# MRCS-Morse-Code-Buzzer-Controller.net
KiCad netlist of a schematic drawn in EAGLE
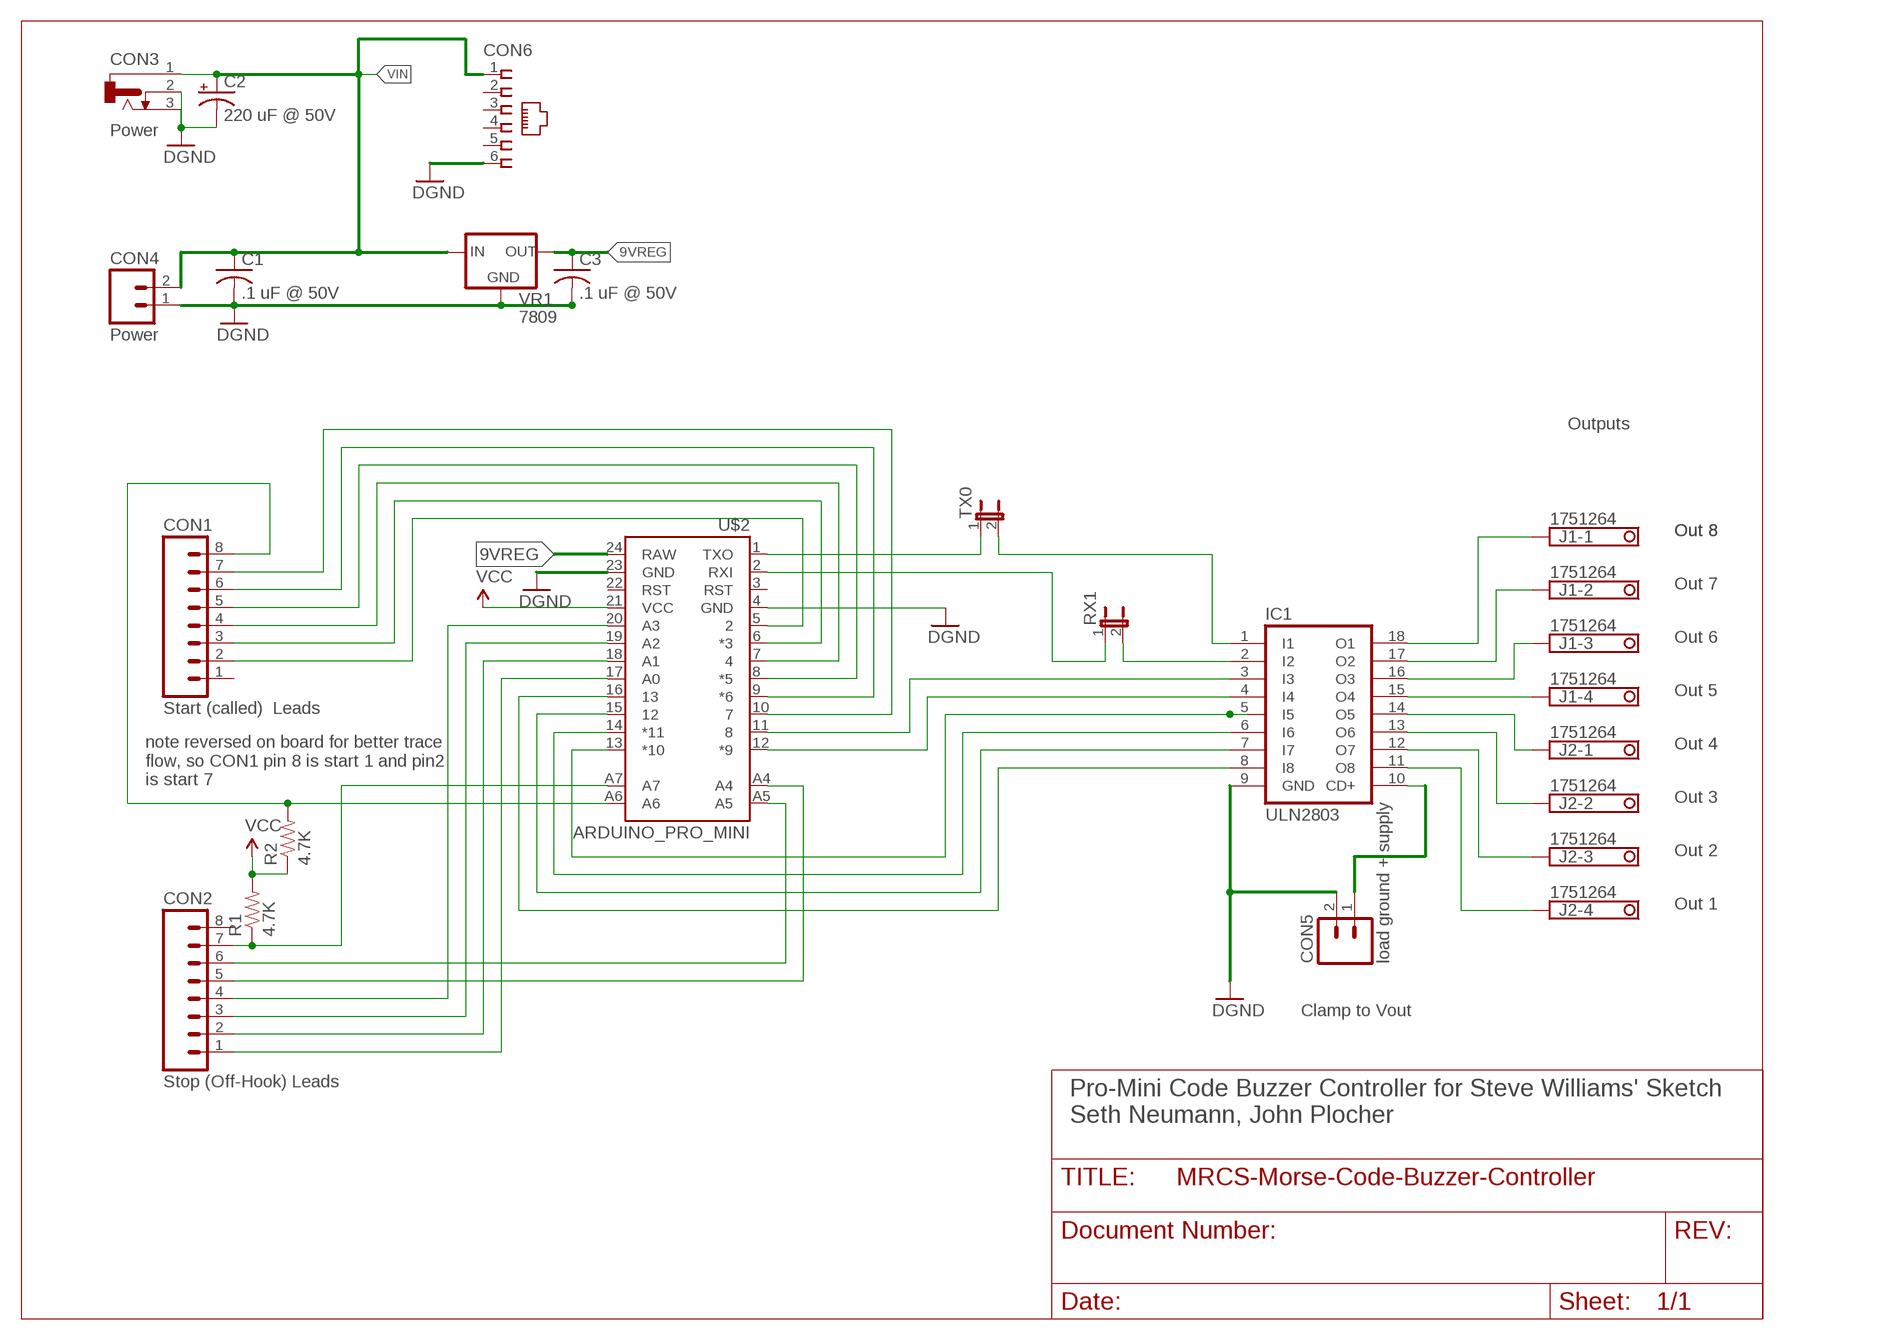
[diagram p0: schematic, sheet 1]

(export (version "E")
  (design (tool "Eeschema 10.0.6"))
  (components
    (comp (ref "C1")
      (value ".1 uF @ 50V")
      (footprint "eagle-import:C025-030X050")
      (libsource (lib "eagle-import") (part "C-US025-030X050"))
    )
    (comp (ref "C2")
      (value "220 uF @ 50V")
      (footprint "eagle-import:E3,5-10")
      (libsource (lib "eagle-import") (part "CPOL-USE3.5-10"))
    )
    (comp (ref "C3")
      (value ".1 uF @ 50V")
      (footprint "eagle-import:C025-030X050")
      (libsource (lib "eagle-import") (part "C-US025-030X050"))
    )
    (comp (ref "CON1")
      (value "Start (called) Leads")
      (footprint "eagle-import:1X08_LOCK")
      (libsource (lib "eagle-import") (part "CONNECTOR-M08LOCK"))
    )
    (comp (ref "CON2")
      (value "Stop (Off-Hook) Leads")
      (footprint "eagle-import:1X08_LOCK")
      (libsource (lib "eagle-import") (part "CONNECTOR-M08LOCK"))
    )
    (comp (ref "CON3")
      (value "Power")
      (footprint "eagle-import:DCJ0202")
      (libsource (lib "eagle-import") (part "CONNECTOR-DC-POWER-RA"))
    )
    (comp (ref "CON4")
      (value "Power")
      (footprint "eagle-import:MSTB2")
      (libsource (lib "eagle-import") (part "CONNECTOR-M02508-LOCK"))
    )
    (comp (ref "CON5")
      (value "load ground + supply")
      (footprint "eagle-import:MSTB2")
      (libsource (lib "eagle-import") (part "CONNECTOR-M02508-LOCK"))
    )
    (comp (ref "CON6")
      (value "CONNECTOR-RJ25-43860-2-MOLEX")
      (footprint "eagle-import:RJ25-INVERTED")
      (libsource (lib "eagle-import") (part "CONNECTOR-RJ25-43860-2-MOLEX"))
    )
    (comp (ref "IC1")
      (value "ULN2803")
      (footprint "eagle-import:DIL18")
      (libsource (lib "eagle-import") (part "ULN2803A"))
    )
    (comp (ref "J1")
      (value "1751264")
      (footprint "eagle-import:1751264")
      (libsource (lib "eagle-import") (part "1751264"))
    )
    (comp (ref "J2")
      (value "1751264")
      (footprint "eagle-import:1751264")
      (libsource (lib "eagle-import") (part "1751264"))
    )
    (comp (ref "R1")
      (value "4.7K")
      (footprint "eagle-import:AXIAL-0.4-RES")
      (libsource (lib "eagle-import") (part "RPTH04"))
    )
    (comp (ref "R2")
      (value "4.7K")
      (footprint "eagle-import:AXIAL-0.4-RES")
      (libsource (lib "eagle-import") (part "RPTH04"))
    )
    (comp (ref "RX1")
      (value "JUMPER-2PTH")
      (footprint "eagle-import:1X02")
      (libsource (lib "eagle-import") (part "JUMPER-2PTH"))
    )
    (comp (ref "TX0")
      (value "JUMPER-2PTH")
      (footprint "eagle-import:1X02")
      (libsource (lib "eagle-import") (part "JUMPER-2PTH"))
    )
    (comp (ref "U$2")
      (value "ARDUINO_PRO_MINI")
      (footprint "eagle-import:ARDUINO_PRO_MINI")
      (libsource (lib "eagle-import") (part "ARDUINO_PRO_MINI"))
    )
    (comp (ref "VR1")
      (value "7809")
      (footprint "eagle-import:TO-220-RA-SINK")
      (libsource (lib "eagle-import") (part "VREG-?-PTH-RA9"))
    )
  )
  (nets
    (net (code "1") (name "9VREG") (class "Default")
      (node (ref "C3") (pin "1") (pinfunction "1_1") (pintype "passive"))
      (node (ref "U$2") (pin "24") (pinfunction "RAW_24") (pintype "bidirectional"))
      (node (ref "VR1") (pin "OUT") (pinfunction "OUT_OUT") (pintype "output"))
    )
    (net (code "2") (name "DGND") (class "Default")
      (node (ref "C1") (pin "2") (pinfunction "2_2") (pintype "passive"))
      (node (ref "C2") (pin "-") (pinfunction "-_-") (pintype "passive"))
      (node (ref "C3") (pin "2") (pinfunction "2_2") (pintype "passive"))
      (node (ref "CON3") (pin "2") (pinfunction "2_2") (pintype "passive"))
      (node (ref "CON3") (pin "3") (pinfunction "3_3") (pintype "passive"))
      (node (ref "CON4") (pin "1") (pinfunction "1_1") (pintype "passive"))
      (node (ref "CON5") (pin "2") (pinfunction "2_2") (pintype "passive"))
      (node (ref "CON6") (pin "6") (pinfunction "6_6") (pintype "passive"))
      (node (ref "IC1") (pin "9") (pinfunction "GND_9") (pintype "power_in"))
      (node (ref "U$2") (pin "23") (pinfunction "GND_23") (pintype "bidirectional"))
      (node (ref "U$2") (pin "4") (pinfunction "GND_4") (pintype "bidirectional"))
      (node (ref "VR1") (pin "GND") (pinfunction "GND_GND") (pintype "input"))
    )
    (net (code "3") (name "Net-(CON2-Pad5)") (class "Default")
      (node (ref "CON2") (pin "5") (pinfunction "5_5") (pintype "passive"))
      (node (ref "U$2") (pin "A4") (pinfunction "A4_A4") (pintype "bidirectional"))
    )
    (net (code "4") (name "Net-(CON2-Pad6)") (class "Default")
      (node (ref "CON2") (pin "6") (pinfunction "6_6") (pintype "passive"))
      (node (ref "U$2") (pin "A5") (pinfunction "A5_A5") (pintype "bidirectional"))
    )
    (net (code "5") (name "Net-(IC1-CD+)") (class "Default")
      (node (ref "CON5") (pin "1") (pinfunction "1_1") (pintype "passive"))
      (node (ref "IC1") (pin "10") (pinfunction "CD+_10") (pintype "passive"))
    )
    (net (code "6") (name "Net-(IC1-I1)") (class "Default")
      (node (ref "IC1") (pin "1") (pinfunction "I1_1") (pintype "input"))
      (node (ref "TX0") (pin "2") (pinfunction "2_2") (pintype "passive"))
    )
    (net (code "7") (name "Net-(IC1-I2)") (class "Default")
      (node (ref "IC1") (pin "2") (pinfunction "I2_2") (pintype "input"))
      (node (ref "RX1") (pin "2") (pinfunction "2_2") (pintype "passive"))
    )
    (net (code "8") (name "Net-(IC1-I3)") (class "Default")
      (node (ref "IC1") (pin "3") (pinfunction "I3_3") (pintype "input"))
      (node (ref "U$2") (pin "11") (pinfunction "8_11") (pintype "bidirectional"))
    )
    (net (code "9") (name "Net-(IC1-I4)") (class "Default")
      (node (ref "IC1") (pin "4") (pinfunction "I4_4") (pintype "input"))
      (node (ref "U$2") (pin "12") (pinfunction "*9_12") (pintype "bidirectional"))
    )
    (net (code "10") (name "Net-(IC1-I5)") (class "Default")
      (node (ref "IC1") (pin "5") (pinfunction "I5_5") (pintype "input"))
      (node (ref "U$2") (pin "13") (pinfunction "*10_13") (pintype "bidirectional"))
    )
    (net (code "11") (name "Net-(IC1-I6)") (class "Default")
      (node (ref "IC1") (pin "6") (pinfunction "I6_6") (pintype "input"))
      (node (ref "U$2") (pin "14") (pinfunction "*11_14") (pintype "bidirectional"))
    )
    (net (code "12") (name "Net-(IC1-I7)") (class "Default")
      (node (ref "IC1") (pin "7") (pinfunction "I7_7") (pintype "input"))
      (node (ref "U$2") (pin "15") (pinfunction "12_15") (pintype "bidirectional"))
    )
    (net (code "13") (name "Net-(IC1-I8)") (class "Default")
      (node (ref "IC1") (pin "8") (pinfunction "I8_8") (pintype "input"))
      (node (ref "U$2") (pin "16") (pinfunction "13_16") (pintype "bidirectional"))
    )
    (net (code "14") (name "Net-(IC1-O1)") (class "Default")
      (node (ref "IC1") (pin "18") (pinfunction "O1_18") (pintype "open_collector"))
      (node (ref "J1") (pin "1") (pinfunction "K_1") (pintype "passive"))
    )
    (net (code "15") (name "Net-(IC1-O2)") (class "Default")
      (node (ref "IC1") (pin "17") (pinfunction "O2_17") (pintype "open_collector"))
      (node (ref "J1") (pin "2") (pinfunction "K_2") (pintype "passive"))
    )
    (net (code "16") (name "Net-(IC1-O3)") (class "Default")
      (node (ref "IC1") (pin "16") (pinfunction "O3_16") (pintype "open_collector"))
      (node (ref "J1") (pin "3") (pinfunction "K_3") (pintype "passive"))
    )
    (net (code "17") (name "Net-(IC1-O4)") (class "Default")
      (node (ref "IC1") (pin "15") (pinfunction "O4_15") (pintype "open_collector"))
      (node (ref "J1") (pin "4") (pinfunction "K_4") (pintype "passive"))
    )
    (net (code "18") (name "Net-(IC1-O5)") (class "Default")
      (node (ref "IC1") (pin "14") (pinfunction "O5_14") (pintype "open_collector"))
      (node (ref "J2") (pin "1") (pinfunction "K_1") (pintype "passive"))
    )
    (net (code "19") (name "Net-(IC1-O6)") (class "Default")
      (node (ref "IC1") (pin "13") (pinfunction "O6_13") (pintype "open_collector"))
      (node (ref "J2") (pin "2") (pinfunction "K_2") (pintype "passive"))
    )
    (net (code "20") (name "Net-(IC1-O7)") (class "Default")
      (node (ref "IC1") (pin "12") (pinfunction "O7_12") (pintype "open_collector"))
      (node (ref "J2") (pin "3") (pinfunction "K_3") (pintype "passive"))
    )
    (net (code "21") (name "Net-(IC1-O8)") (class "Default")
      (node (ref "IC1") (pin "11") (pinfunction "O8_11") (pintype "open_collector"))
      (node (ref "J2") (pin "4") (pinfunction "K_4") (pintype "passive"))
    )
    (net (code "22") (name "Net-(R1-1)") (class "Default")
      (node (ref "CON2") (pin "7") (pinfunction "7_7") (pintype "passive"))
      (node (ref "R1") (pin "P$1") (pinfunction "1_P$1") (pintype "passive"))
      (node (ref "U$2") (pin "A7") (pinfunction "A7_A7") (pintype "bidirectional"))
    )
    (net (code "23") (name "Net-(R2-2)") (class "Default")
      (node (ref "CON1") (pin "8") (pinfunction "8_8") (pintype "passive"))
      (node (ref "R2") (pin "P$2") (pinfunction "2_P$2") (pintype "passive"))
      (node (ref "U$2") (pin "A6") (pinfunction "A6_A6") (pintype "bidirectional"))
    )
    (net (code "24") (name "Net-(U$2-*3)") (class "Default")
      (node (ref "CON1") (pin "3") (pinfunction "3_3") (pintype "passive"))
      (node (ref "U$2") (pin "6") (pinfunction "*3_6") (pintype "bidirectional"))
    )
    (net (code "25") (name "Net-(U$2-*5)") (class "Default")
      (node (ref "CON1") (pin "5") (pinfunction "5_5") (pintype "passive"))
      (node (ref "U$2") (pin "8") (pinfunction "*5_8") (pintype "bidirectional"))
    )
    (net (code "26") (name "Net-(U$2-*6)") (class "Default")
      (node (ref "CON1") (pin "6") (pinfunction "6_6") (pintype "passive"))
      (node (ref "U$2") (pin "9") (pinfunction "*6_9") (pintype "bidirectional"))
    )
    (net (code "27") (name "Net-(U$2-2)") (class "Default")
      (node (ref "CON1") (pin "2") (pinfunction "2_2") (pintype "passive"))
      (node (ref "U$2") (pin "5") (pinfunction "2_5") (pintype "bidirectional"))
    )
    (net (code "28") (name "Net-(U$2-4)") (class "Default")
      (node (ref "CON1") (pin "4") (pinfunction "4_4") (pintype "passive"))
      (node (ref "U$2") (pin "7") (pinfunction "4_7") (pintype "bidirectional"))
    )
    (net (code "29") (name "Net-(U$2-7)") (class "Default")
      (node (ref "CON1") (pin "7") (pinfunction "7_7") (pintype "passive"))
      (node (ref "U$2") (pin "10") (pinfunction "7_10") (pintype "bidirectional"))
    )
    (net (code "30") (name "Net-(U$2-A0)") (class "Default")
      (node (ref "CON2") (pin "1") (pinfunction "1_1") (pintype "passive"))
      (node (ref "U$2") (pin "17") (pinfunction "A0_17") (pintype "bidirectional"))
    )
    (net (code "31") (name "Net-(U$2-A1)") (class "Default")
      (node (ref "CON2") (pin "2") (pinfunction "2_2") (pintype "passive"))
      (node (ref "U$2") (pin "18") (pinfunction "A1_18") (pintype "bidirectional"))
    )
    (net (code "32") (name "Net-(U$2-A2)") (class "Default")
      (node (ref "CON2") (pin "3") (pinfunction "3_3") (pintype "passive"))
      (node (ref "U$2") (pin "19") (pinfunction "A2_19") (pintype "bidirectional"))
    )
    (net (code "33") (name "Net-(U$2-A3)") (class "Default")
      (node (ref "CON2") (pin "4") (pinfunction "4_4") (pintype "passive"))
      (node (ref "U$2") (pin "20") (pinfunction "A3_20") (pintype "bidirectional"))
    )
    (net (code "34") (name "Net-(U$2-RXI)") (class "Default")
      (node (ref "RX1") (pin "1") (pinfunction "1_1") (pintype "passive"))
      (node (ref "U$2") (pin "2") (pinfunction "RXI_2") (pintype "bidirectional"))
    )
    (net (code "35") (name "Net-(U$2-TXO)") (class "Default")
      (node (ref "TX0") (pin "1") (pinfunction "1_1") (pintype "passive"))
      (node (ref "U$2") (pin "1") (pinfunction "TXO_1") (pintype "bidirectional"))
    )
    (net (code "36") (name "VCC") (class "Default")
      (node (ref "R1") (pin "P$2") (pinfunction "2_P$2") (pintype "passive"))
      (node (ref "R2") (pin "P$1") (pinfunction "1_P$1") (pintype "passive"))
      (node (ref "U$2") (pin "21") (pinfunction "VCC_21") (pintype "bidirectional"))
    )
    (net (code "37") (name "VIN") (class "Default")
      (node (ref "C1") (pin "1") (pinfunction "1_1") (pintype "passive"))
      (node (ref "C2") (pin "+") (pinfunction "+_+") (pintype "passive"))
      (node (ref "CON3") (pin "1") (pinfunction "1_1") (pintype "passive"))
      (node (ref "CON4") (pin "2") (pinfunction "2_2") (pintype "passive"))
      (node (ref "CON6") (pin "1") (pinfunction "1_1") (pintype "passive"))
      (node (ref "VR1") (pin "IN") (pinfunction "IN_IN") (pintype "input"))
    )
    (net (code "38") (name "unconnected-(CON1-Pad1)") (class "Default")
      (node (ref "CON1") (pin "1") (pinfunction "1_1") (pintype "passive"))
    )
    (net (code "39") (name "unconnected-(CON2-Pad8)") (class "Default")
      (node (ref "CON2") (pin "8") (pinfunction "8_8") (pintype "passive"))
    )
    (net (code "40") (name "unconnected-(CON6-Pad2)") (class "Default")
      (node (ref "CON6") (pin "2") (pinfunction "2_2") (pintype "passive"))
    )
    (net (code "41") (name "unconnected-(CON6-Pad3)") (class "Default")
      (node (ref "CON6") (pin "3") (pinfunction "3_3") (pintype "passive"))
    )
    (net (code "42") (name "unconnected-(CON6-Pad4)") (class "Default")
      (node (ref "CON6") (pin "4") (pinfunction "4_4") (pintype "passive"))
    )
    (net (code "43") (name "unconnected-(CON6-Pad5)") (class "Default")
      (node (ref "CON6") (pin "5") (pinfunction "5_5") (pintype "passive"))
    )
    (net (code "44") (name "unconnected-(U$2-RST-Pad3)") (class "Default")
      (node (ref "U$2") (pin "3") (pinfunction "RST_3") (pintype "bidirectional"))
    )
    (net (code "45") (name "unconnected-(U$2-RST-Pad22)") (class "Default")
      (node (ref "U$2") (pin "22") (pinfunction "RST_22") (pintype "bidirectional"))
    )
  )
)
